# uv-dosimeter-featherwing-mk-2_1.net
KiCad netlist of a schematic drawn in EAGLE
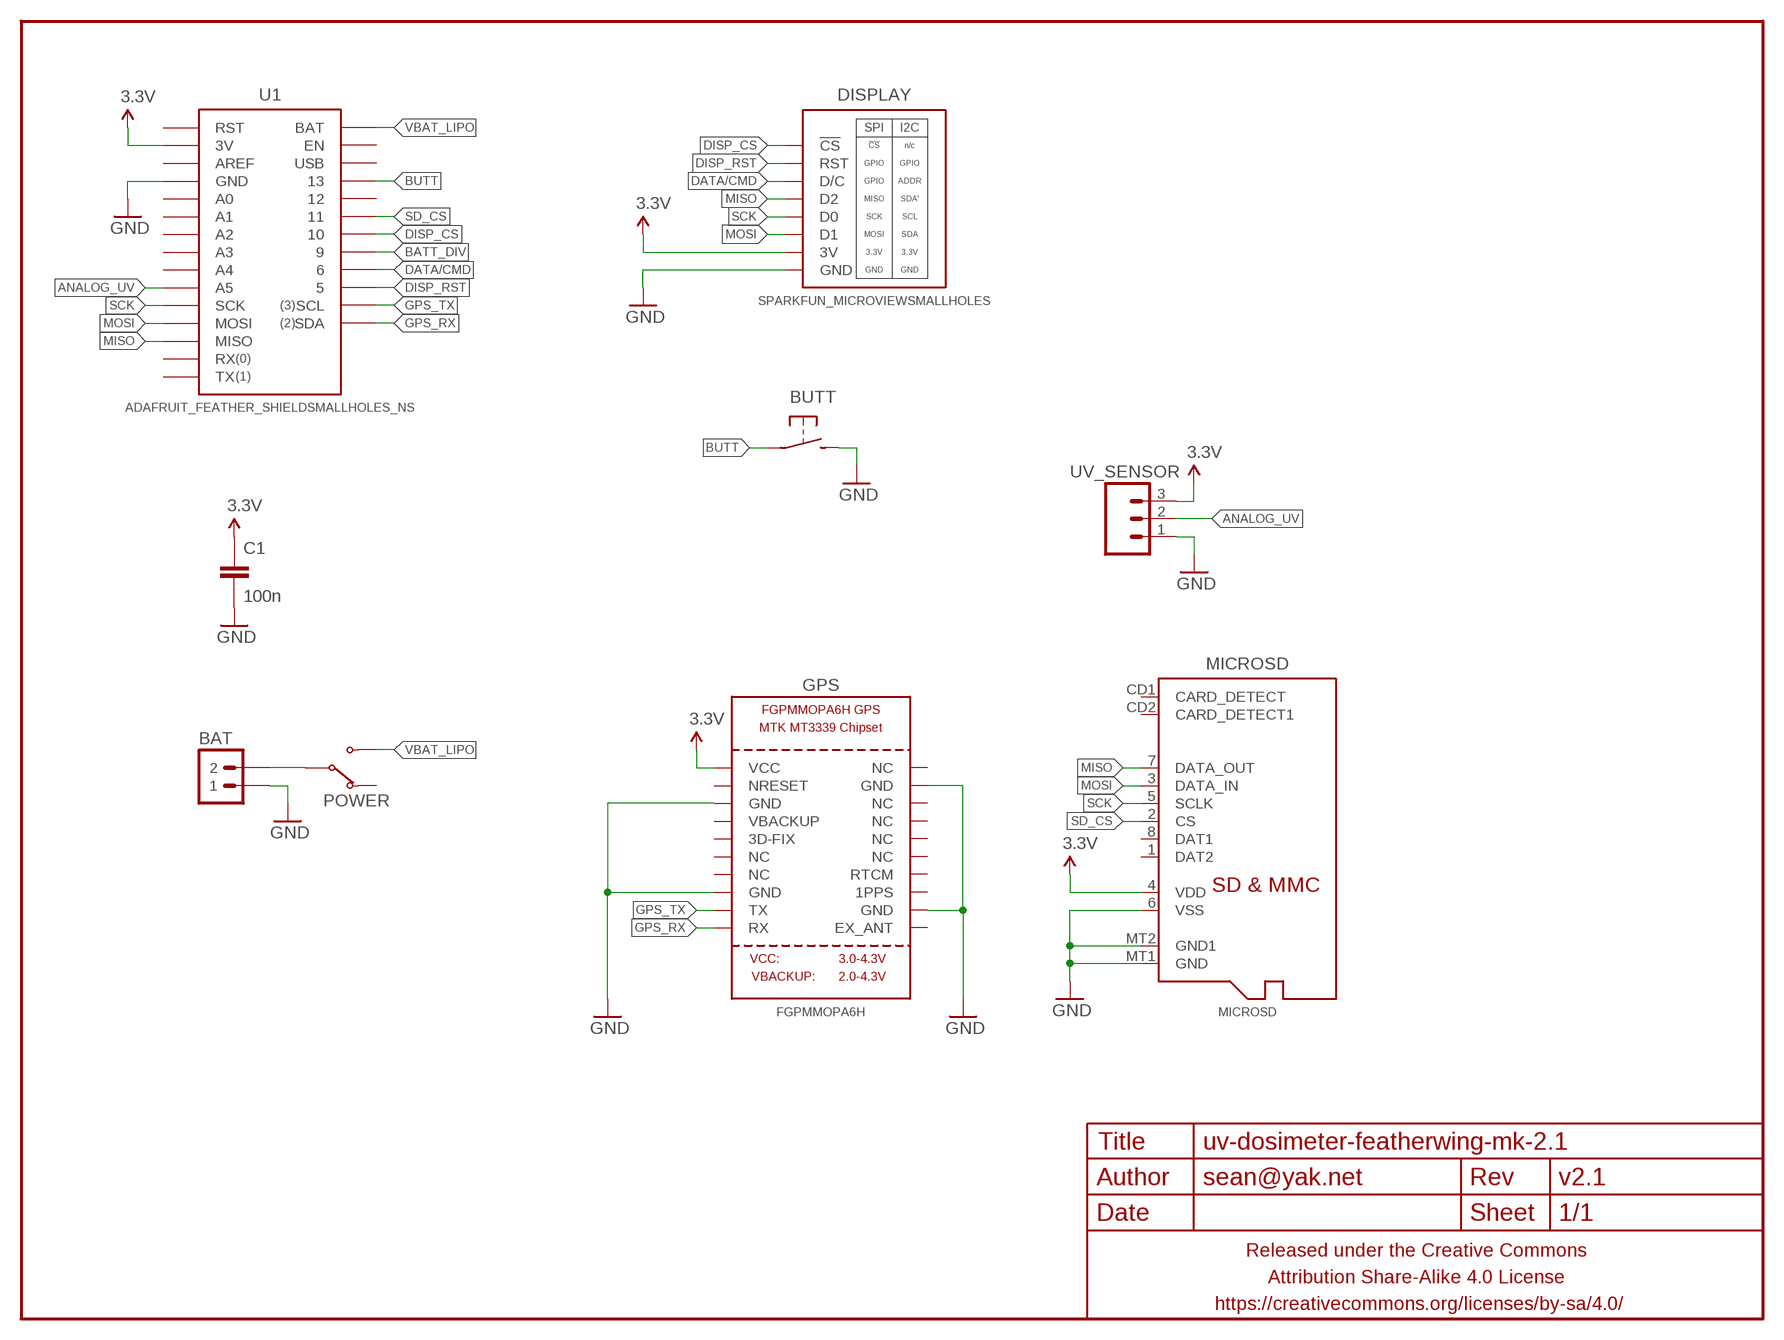
[diagram p0: schematic, sheet 1]

(export (version "E")
  (design (tool "Eeschema 10.0.6"))
  (components
    (comp (ref "BAT")
      (value "M02JST-2MM-SMT")
      (footprint "eagle-import:JST-2-SMD")
      (libsource (lib "eagle-import") (part "M02JST-2MM-SMT"))
    )
    (comp (ref "BUTT")
      (value "SPST-NO-TACT3MM-PTH-SMALL-PADS")
      (footprint "eagle-import:DTS-3-SMALL-PADS")
      (libsource (lib "eagle-import") (part "SPST-NO-TACT3MM-PTH-SMALL-PADS"))
    )
    (comp (ref "C1")
      (value "100n")
      (footprint "eagle-import:C0603")
      (libsource (lib "eagle-import") (part "CAPACITOR-CERAMICC0603"))
    )
    (comp (ref "DISPLAY")
      (value "SPARKFUN_MICROVIEWSMALLHOLES")
      (footprint "eagle-import:SPARKFUN-MICROVIEW-SMALLHOLES")
      (libsource (lib "eagle-import") (part "SPARKFUN_MICROVIEWSMALLHOLES"))
    )
    (comp (ref "FRAME1")
      (value "FRAME-LETTERNO_PACKAGE")
      (footprint "eagle-import:DUMMY")
      (fields (field (name "DESIGNER") "sean@yak.net") (field (name "VERSION") "v2.1"))
      (libsource (lib "eagle-import") (part "FRAME-LETTERNO_PACKAGE"))
    )
    (comp (ref "GPS")
      (value "FGPMMOPA6H")
      (footprint "eagle-import:FGPMMOPA6H")
      (libsource (lib "eagle-import") (part "GPS_FGPMMOPA6H"))
    )
    (comp (ref "MICROSD")
      (value "MICROSD")
      (footprint "eagle-import:MICROSD")
      (libsource (lib "eagle-import") (part "MICROSD"))
    )
    (comp (ref "POWER")
      (value "SWITCH-SPDTPTH-VERT-2.54MM")
      (footprint "eagle-import:SWITCH-SPDT")
      (libsource (lib "eagle-import") (part "SWITCH-SPDTPTH-VERT-2.54MM"))
    )
    (comp (ref "U1")
      (value "ADAFRUIT_FEATHER_SHIELDSMALLHOLES_NS")
      (footprint "eagle-import:ADAFRUIT_FEATHER_SMALLHOLES_NS")
      (libsource (lib "eagle-import") (part "ADAFRUIT_FEATHER_SHIELDSMALLHOLES_NS"))
    )
    (comp (ref "UV_SENSOR")
      (value "M03PTH-CENTERED")
      (footprint "eagle-import:1X03-CENTERED")
      (libsource (lib "eagle-import") (part "M03PTH-CENTERED"))
    )
  )
  (nets
    (net (code "1") (name "3.3V") (class "Default")
      (node (ref "C1") (pin "1") (pinfunction "1_1") (pintype "passive"))
      (node (ref "DISPLAY") (pin "3V") (pinfunction "3V_3V") (pintype "bidirectional"))
      (node (ref "GPS") (pin "P$1") (pinfunction "VCC_P$1") (pintype "bidirectional"))
      (node (ref "MICROSD") (pin "4") (pinfunction "VDD_4") (pintype "power_in"))
      (node (ref "U1") (pin "3V") (pinfunction "3V_3V") (pintype "bidirectional"))
      (node (ref "UV_SENSOR") (pin "3") (pinfunction "3_3") (pintype "passive"))
    )
    (net (code "2") (name "ANALOG_UV") (class "Default")
      (node (ref "U1") (pin "A5") (pinfunction "A5_A5") (pintype "bidirectional"))
      (node (ref "UV_SENSOR") (pin "2") (pinfunction "2_2") (pintype "passive"))
    )
    (net (code "3") (name "BATT_DIV") (class "Default")
      (node (ref "U1") (pin "9") (pinfunction "9_9") (pintype "bidirectional"))
    )
    (net (code "4") (name "BUTT") (class "Default")
      (node (ref "BUTT") (pin "1") (pinfunction "1_1") (pintype "passive"))
      (node (ref "U1") (pin "13") (pinfunction "13_13") (pintype "bidirectional"))
    )
    (net (code "5") (name "DATA{slash}CMD") (class "Default")
      (node (ref "DISPLAY") (pin "D/C") (pinfunction "D/C_D/C") (pintype "bidirectional"))
      (node (ref "U1") (pin "6") (pinfunction "6_6") (pintype "bidirectional"))
    )
    (net (code "6") (name "DISP_CS") (class "Default")
      (node (ref "DISPLAY") (pin "CS") (pinfunction "~{CS}_CS") (pintype "bidirectional"))
      (node (ref "U1") (pin "10") (pinfunction "10_10") (pintype "bidirectional"))
    )
    (net (code "7") (name "DISP_RST") (class "Default")
      (node (ref "DISPLAY") (pin "RST") (pinfunction "RST_RST") (pintype "bidirectional"))
      (node (ref "U1") (pin "5") (pinfunction "5_5") (pintype "bidirectional"))
    )
    (net (code "8") (name "GND") (class "Default")
      (node (ref "BAT") (pin "2") (pinfunction "1_2") (pintype "passive"))
      (node (ref "BUTT") (pin "2") (pinfunction "2_2") (pintype "passive"))
      (node (ref "C1") (pin "2") (pinfunction "2_2") (pintype "passive"))
      (node (ref "DISPLAY") (pin "GND") (pinfunction "GND_GND") (pintype "bidirectional"))
      (node (ref "GPS") (pin "P$12") (pinfunction "GND_P$12") (pintype "bidirectional"))
      (node (ref "GPS") (pin "P$19") (pinfunction "GND_P$19") (pintype "bidirectional"))
      (node (ref "GPS") (pin "P$3") (pinfunction "GND_P$3") (pintype "bidirectional"))
      (node (ref "GPS") (pin "P$8") (pinfunction "GND_P$8") (pintype "bidirectional"))
      (node (ref "MICROSD") (pin "6") (pinfunction "VSS_6") (pintype "power_in"))
      (node (ref "MICROSD") (pin "MT1") (pinfunction "GND_MT1") (pintype "power_in"))
      (node (ref "MICROSD") (pin "MT2") (pinfunction "GND1_MT2") (pintype "power_in"))
      (node (ref "U1") (pin "GND@0") (pinfunction "GND_GND@0") (pintype "bidirectional"))
      (node (ref "U1") (pin "GND@1") (pinfunction "GND_GND@1") (pintype "bidirectional"))
      (node (ref "UV_SENSOR") (pin "1") (pinfunction "1_1") (pintype "passive"))
    )
    (net (code "9") (name "GPS_RX") (class "Default")
      (node (ref "GPS") (pin "P$10") (pinfunction "RX_P$10") (pintype "bidirectional"))
      (node (ref "U1") (pin "SDA") (pinfunction "SDA_SDA") (pintype "bidirectional"))
    )
    (net (code "10") (name "GPS_TX") (class "Default")
      (node (ref "GPS") (pin "P$9") (pinfunction "TX_P$9") (pintype "bidirectional"))
      (node (ref "U1") (pin "SCL") (pinfunction "SCL_SCL") (pintype "bidirectional"))
    )
    (net (code "11") (name "MISO") (class "Default")
      (node (ref "DISPLAY") (pin "D2") (pinfunction "D2_D2") (pintype "bidirectional"))
      (node (ref "MICROSD") (pin "7") (pinfunction "DATA_OUT_7") (pintype "output"))
      (node (ref "U1") (pin "MISO") (pinfunction "MISO_MISO") (pintype "bidirectional"))
    )
    (net (code "12") (name "MOSI") (class "Default")
      (node (ref "DISPLAY") (pin "D1") (pinfunction "D1_D1") (pintype "bidirectional"))
      (node (ref "MICROSD") (pin "3") (pinfunction "DATA_IN_3") (pintype "input"))
      (node (ref "U1") (pin "MOSI") (pinfunction "MOSI_MOSI") (pintype "bidirectional"))
    )
    (net (code "13") (name "Net-(BAT-2)") (class "Default")
      (node (ref "BAT") (pin "1") (pinfunction "2_1") (pintype "passive"))
      (node (ref "POWER") (pin "2") (pinfunction "COM_2") (pintype "passive"))
    )
    (net (code "14") (name "SCK") (class "Default")
      (node (ref "DISPLAY") (pin "D0") (pinfunction "D0_D0") (pintype "bidirectional"))
      (node (ref "MICROSD") (pin "5") (pinfunction "SCLK_5") (pintype "input"))
      (node (ref "U1") (pin "SCK") (pinfunction "SCK_SCK") (pintype "bidirectional"))
    )
    (net (code "15") (name "SD_CS") (class "Default")
      (node (ref "MICROSD") (pin "2") (pinfunction "CS_2") (pintype "input"))
      (node (ref "U1") (pin "11") (pinfunction "11_11") (pintype "bidirectional"))
    )
    (net (code "16") (name "VBAT_LIPO") (class "Default")
      (node (ref "POWER") (pin "3") (pinfunction "NO_3") (pintype "passive"))
      (node (ref "U1") (pin "BAT") (pinfunction "BAT_BAT") (pintype "bidirectional"))
    )
    (net (code "17") (name "unconnected-(GPS-1PPS-PadP$13)") (class "Default")
      (node (ref "GPS") (pin "P$13") (pinfunction "1PPS_P$13") (pintype "bidirectional"))
    )
    (net (code "18") (name "unconnected-(GPS-3D-FIX-PadP$5)") (class "Default")
      (node (ref "GPS") (pin "P$5") (pinfunction "3D-FIX_P$5") (pintype "bidirectional"))
    )
    (net (code "19") (name "unconnected-(GPS-EX_ANT-PadP$11)") (class "Default")
      (node (ref "GPS") (pin "P$11") (pinfunction "EX_ANT_P$11") (pintype "bidirectional"))
    )
    (net (code "20") (name "unconnected-(GPS-NC-PadP$6)") (class "Default")
      (node (ref "GPS") (pin "P$6") (pinfunction "NC_P$6") (pintype "bidirectional"))
    )
    (net (code "21") (name "unconnected-(GPS-NC-PadP$7)") (class "Default")
      (node (ref "GPS") (pin "P$7") (pinfunction "NC_P$7") (pintype "bidirectional"))
    )
    (net (code "22") (name "unconnected-(GPS-NC-PadP$15)") (class "Default")
      (node (ref "GPS") (pin "P$15") (pinfunction "NC_P$15") (pintype "bidirectional"))
    )
    (net (code "23") (name "unconnected-(GPS-NC-PadP$16)") (class "Default")
      (node (ref "GPS") (pin "P$16") (pinfunction "NC_P$16") (pintype "bidirectional"))
    )
    (net (code "24") (name "unconnected-(GPS-NC-PadP$17)") (class "Default")
      (node (ref "GPS") (pin "P$17") (pinfunction "NC_P$17") (pintype "bidirectional"))
    )
    (net (code "25") (name "unconnected-(GPS-NC-PadP$18)") (class "Default")
      (node (ref "GPS") (pin "P$18") (pinfunction "NC_P$18") (pintype "bidirectional"))
    )
    (net (code "26") (name "unconnected-(GPS-NC-PadP$20)") (class "Default")
      (node (ref "GPS") (pin "P$20") (pinfunction "NC_P$20") (pintype "bidirectional"))
    )
    (net (code "27") (name "unconnected-(GPS-NRESET-PadP$2)") (class "Default")
      (node (ref "GPS") (pin "P$2") (pinfunction "NRESET_P$2") (pintype "bidirectional"))
    )
    (net (code "28") (name "unconnected-(GPS-RTCM-PadP$14)") (class "Default")
      (node (ref "GPS") (pin "P$14") (pinfunction "RTCM_P$14") (pintype "bidirectional"))
    )
    (net (code "29") (name "unconnected-(GPS-VBACKUP-PadP$4)") (class "Default")
      (node (ref "GPS") (pin "P$4") (pinfunction "VBACKUP_P$4") (pintype "bidirectional"))
    )
    (net (code "30") (name "unconnected-(MICROSD-CARD_DETECT-PadCD1)") (class "Default")
      (node (ref "MICROSD") (pin "CD1") (pinfunction "CARD_DETECT_CD1") (pintype "passive"))
    )
    (net (code "31") (name "unconnected-(MICROSD-CARD_DETECT1-PadCD2)") (class "Default")
      (node (ref "MICROSD") (pin "CD2") (pinfunction "CARD_DETECT1_CD2") (pintype "passive"))
    )
    (net (code "32") (name "unconnected-(MICROSD-DAT1-Pad8)") (class "Default")
      (node (ref "MICROSD") (pin "8") (pinfunction "DAT1_8") (pintype "bidirectional"))
    )
    (net (code "33") (name "unconnected-(MICROSD-DAT2-Pad1)") (class "Default")
      (node (ref "MICROSD") (pin "1") (pinfunction "DAT2_1") (pintype "bidirectional"))
    )
    (net (code "34") (name "unconnected-(POWER-NC-Pad1)") (class "Default")
      (node (ref "POWER") (pin "1") (pinfunction "NC_1") (pintype "passive"))
    )
    (net (code "35") (name "unconnected-(U1-Pad12)") (class "Default")
      (node (ref "U1") (pin "12") (pinfunction "12_12") (pintype "bidirectional"))
    )
    (net (code "36") (name "unconnected-(U1-PadA0)") (class "Default")
      (node (ref "U1") (pin "A0") (pinfunction "A0_A0") (pintype "bidirectional"))
    )
    (net (code "37") (name "unconnected-(U1-PadA1)") (class "Default")
      (node (ref "U1") (pin "A1") (pinfunction "A1_A1") (pintype "bidirectional"))
    )
    (net (code "38") (name "unconnected-(U1-PadA2)") (class "Default")
      (node (ref "U1") (pin "A2") (pinfunction "A2_A2") (pintype "bidirectional"))
    )
    (net (code "39") (name "unconnected-(U1-PadA3)") (class "Default")
      (node (ref "U1") (pin "A3") (pinfunction "A3_A3") (pintype "bidirectional"))
    )
    (net (code "40") (name "unconnected-(U1-PadA4)") (class "Default")
      (node (ref "U1") (pin "A4") (pinfunction "A4_A4") (pintype "bidirectional"))
    )
    (net (code "41") (name "unconnected-(U1-PadAREF)") (class "Default")
      (node (ref "U1") (pin "AREF") (pinfunction "AREF_AREF") (pintype "bidirectional"))
    )
    (net (code "42") (name "unconnected-(U1-PadEN)") (class "Default")
      (node (ref "U1") (pin "EN") (pinfunction "EN_EN") (pintype "bidirectional"))
    )
    (net (code "43") (name "unconnected-(U1-PadRST)") (class "Default")
      (node (ref "U1") (pin "RST") (pinfunction "RST_RST") (pintype "bidirectional"))
    )
    (net (code "44") (name "unconnected-(U1-PadRX)") (class "Default")
      (node (ref "U1") (pin "RX") (pinfunction "RX_RX") (pintype "bidirectional"))
    )
    (net (code "45") (name "unconnected-(U1-PadTX)") (class "Default")
      (node (ref "U1") (pin "TX") (pinfunction "TX_TX") (pintype "bidirectional"))
    )
    (net (code "46") (name "unconnected-(U1-PadUSB)") (class "Default")
      (node (ref "U1") (pin "USB") (pinfunction "USB_USB") (pintype "bidirectional"))
    )
  )
)
